# Main-v6_0.net
KiCad netlist of a schematic drawn in EAGLE
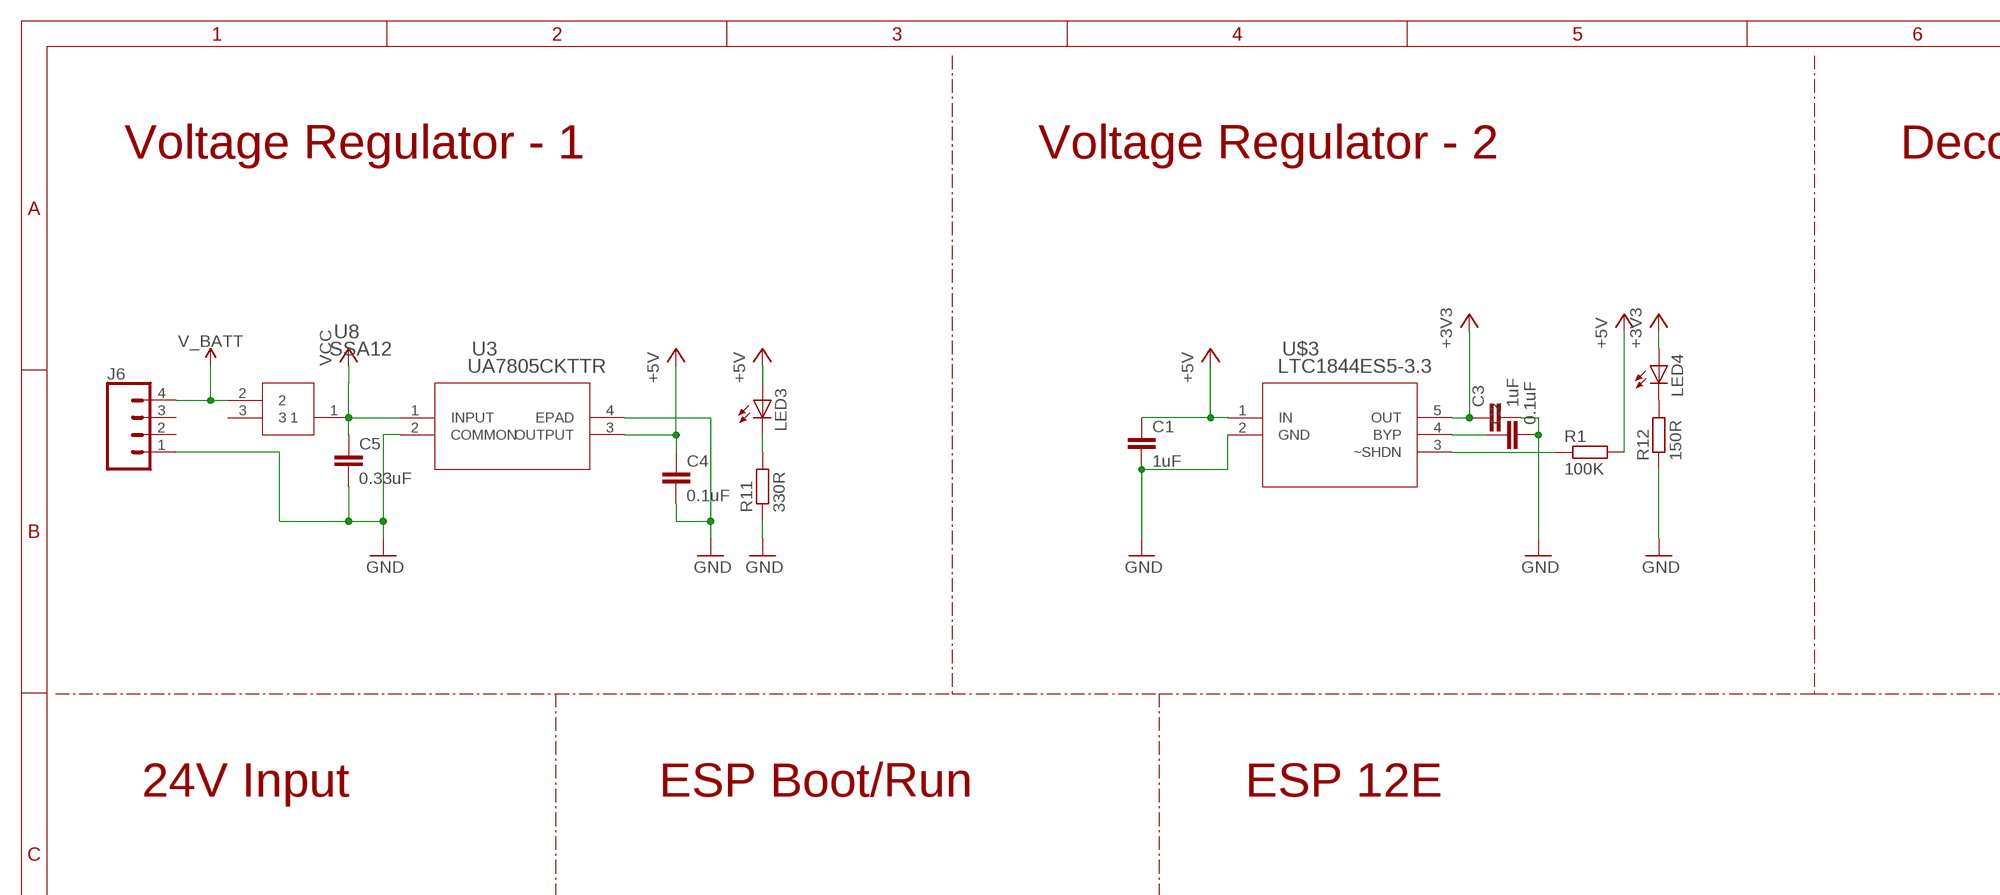
[diagram p0: schematic, sheet 1, part 1 of 3]
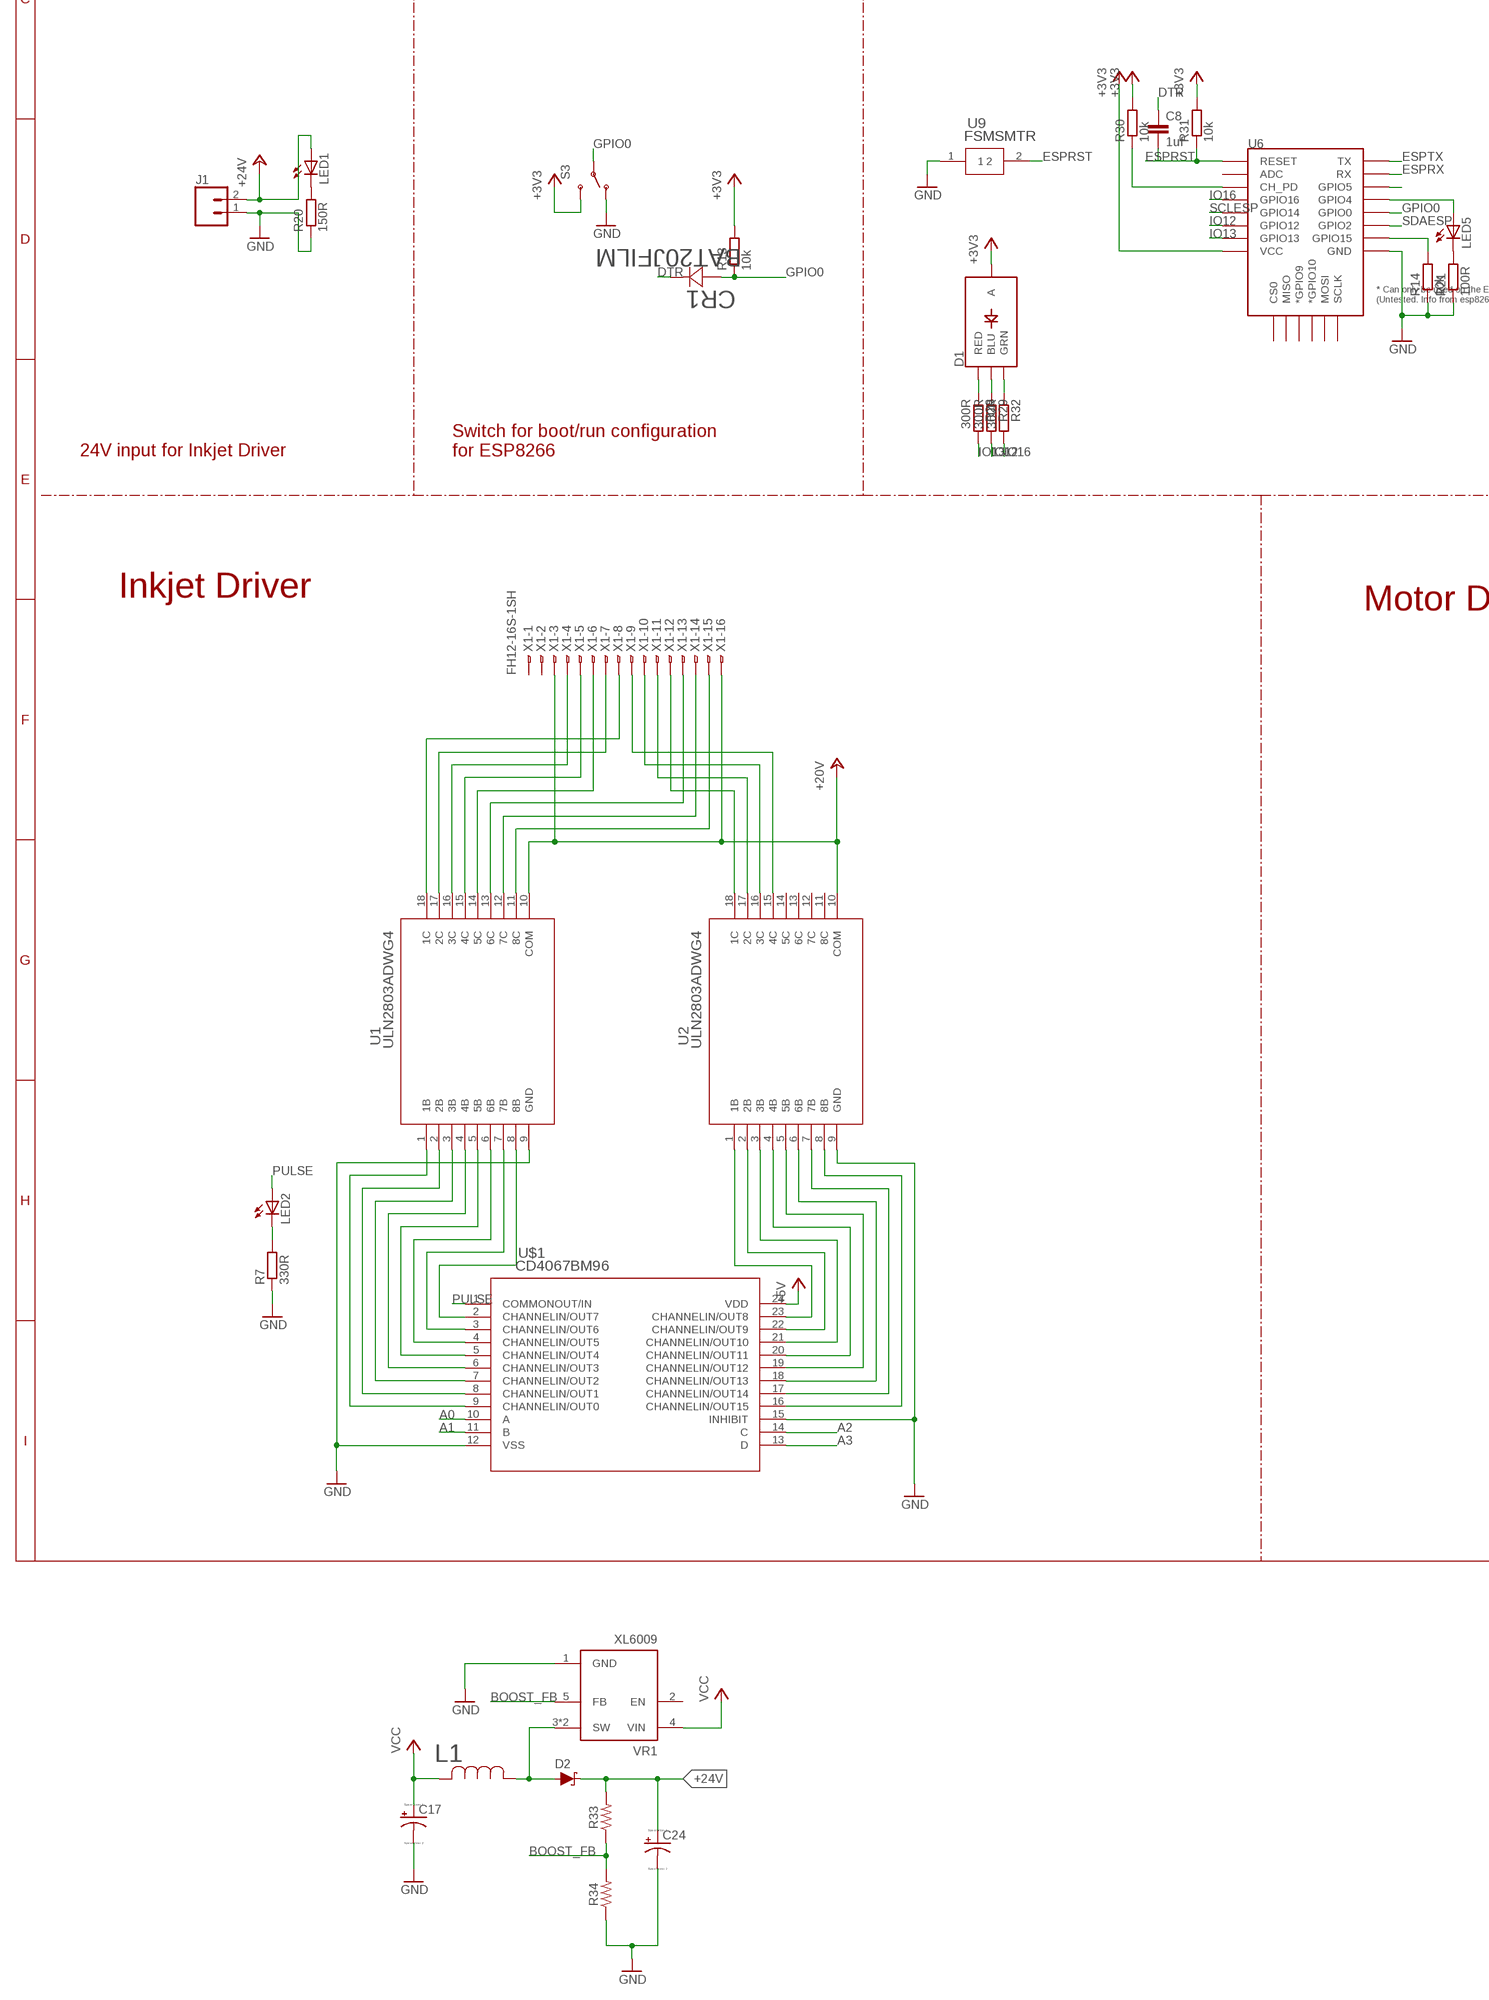
[diagram p1: schematic, sheet 1, part 2 of 3]
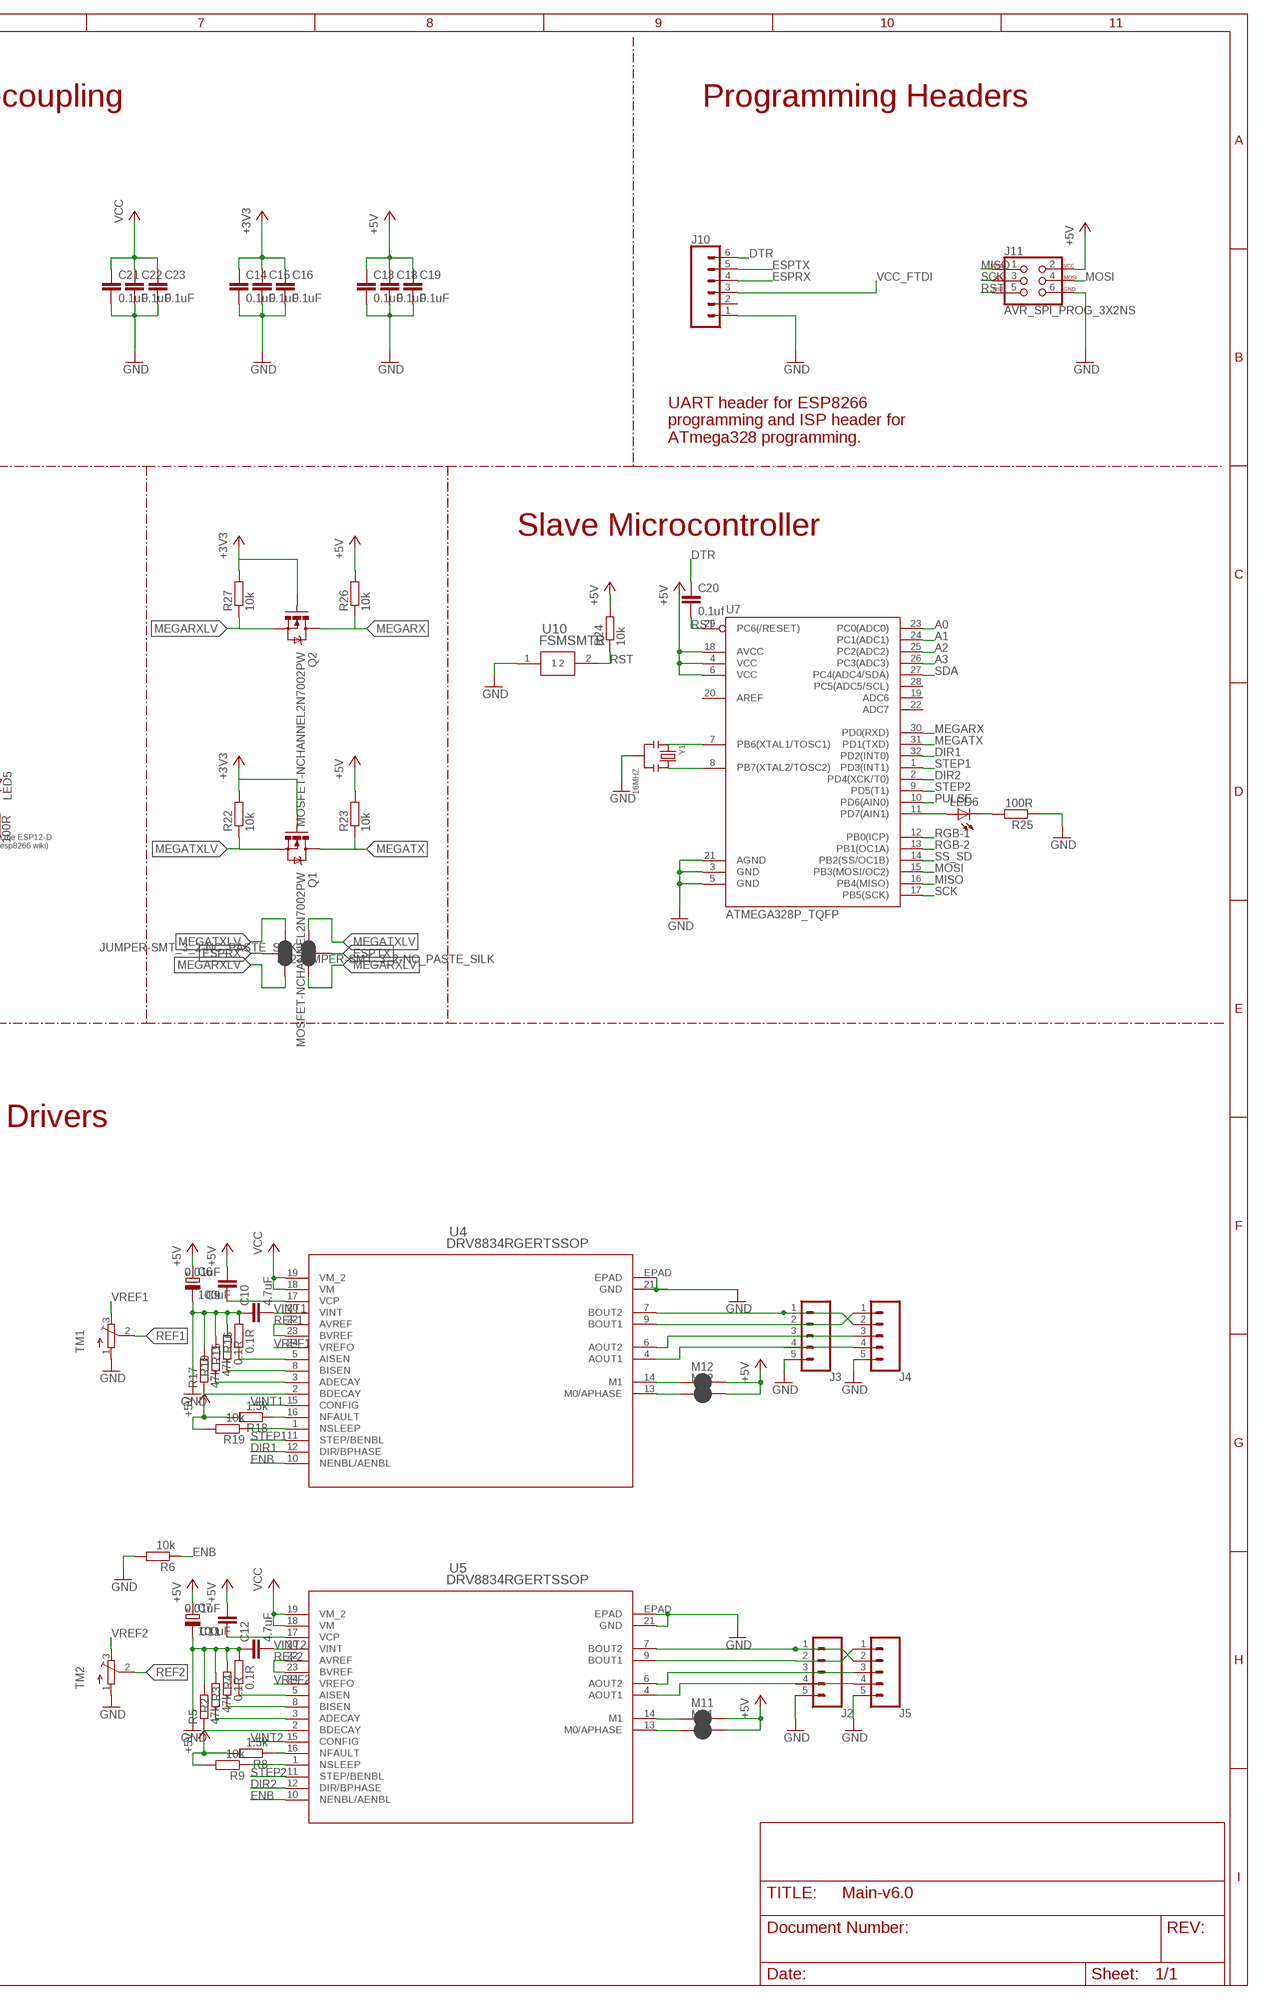
[diagram p2: schematic, sheet 1, part 3 of 3]

(export (version "E")
  (design (tool "Eeschema 10.0.6"))
  (components
    (comp (ref "C1")
      (value "1uF")
      (footprint "eagle-import:C0603")
      (libsource (lib "eagle-import") (part "C-EUC0603"))
    )
    (comp (ref "C2")
      (value "0.1uF")
      (footprint "eagle-import:C0603")
      (libsource (lib "eagle-import") (part "C-EUC0603"))
    )
    (comp (ref "C3")
      (value "1uF")
      (footprint "eagle-import:C0603")
      (libsource (lib "eagle-import") (part "C-EUC0603"))
    )
    (comp (ref "C4")
      (value "0.1uF")
      (footprint "eagle-import:C0603")
      (libsource (lib "eagle-import") (part "C-EUC0603"))
    )
    (comp (ref "C5")
      (value "0.33uF")
      (footprint "eagle-import:C0603")
      (libsource (lib "eagle-import") (part "C-EUC0603"))
    )
    (comp (ref "C6")
      (value "100uF")
      (footprint "eagle-import:E5-5")
      (libsource (lib "eagle-import") (part "CPOL-EUE5-5"))
    )
    (comp (ref "C7")
      (value "100uF")
      (footprint "eagle-import:E5-5")
      (libsource (lib "eagle-import") (part "CPOL-EUE5-5"))
    )
    (comp (ref "C8")
      (value "1uf")
      (footprint "eagle-import:C0603")
      (libsource (lib "eagle-import") (part "resistor_348_C-EUC0603"))
    )
    (comp (ref "C9")
      (value "0.01uF")
      (footprint "eagle-import:C0603K")
      (libsource (lib "eagle-import") (part "resistor_348_C-EUC0603K"))
    )
    (comp (ref "C10")
      (value "4.7uF")
      (footprint "eagle-import:C0603K")
      (libsource (lib "eagle-import") (part "resistor_348_C-EUC0603K"))
    )
    (comp (ref "C11")
      (value "0.01uF")
      (footprint "eagle-import:C0603K")
      (libsource (lib "eagle-import") (part "resistor_348_C-EUC0603K"))
    )
    (comp (ref "C12")
      (value "4.7uF")
      (footprint "eagle-import:C0603K")
      (libsource (lib "eagle-import") (part "resistor_348_C-EUC0603K"))
    )
    (comp (ref "C13")
      (value "0.1uF")
      (footprint "eagle-import:C0603")
      (libsource (lib "eagle-import") (part "C-EUC0603"))
    )
    (comp (ref "C14")
      (value "0.1uF")
      (footprint "eagle-import:C0603")
      (libsource (lib "eagle-import") (part "C-EUC0603"))
    )
    (comp (ref "C15")
      (value "0.1uF")
      (footprint "eagle-import:C0603")
      (libsource (lib "eagle-import") (part "C-EUC0603"))
    )
    (comp (ref "C16")
      (value "0.1uF")
      (footprint "eagle-import:C0603")
      (libsource (lib "eagle-import") (part "C-EUC0603"))
    )
    (comp (ref "C17")
      (value "220uF")
      (footprint "eagle-import:PANASONIC_G")
      (libsource (lib "eagle-import") (part "CPOL-USG"))
    )
    (comp (ref "C18")
      (value "0.1uF")
      (footprint "eagle-import:C0603")
      (libsource (lib "eagle-import") (part "C-EUC0603"))
    )
    (comp (ref "C19")
      (value "0.1uF")
      (footprint "eagle-import:C0603")
      (libsource (lib "eagle-import") (part "C-EUC0603"))
    )
    (comp (ref "C20")
      (value "0.1uf")
      (footprint "eagle-import:C0603")
      (libsource (lib "eagle-import") (part "resistor_348_C-EUC0603"))
    )
    (comp (ref "C21")
      (value "0.1uF")
      (footprint "eagle-import:C0603")
      (libsource (lib "eagle-import") (part "C-EUC0603"))
    )
    (comp (ref "C22")
      (value "0.1uF")
      (footprint "eagle-import:C0603")
      (libsource (lib "eagle-import") (part "C-EUC0603"))
    )
    (comp (ref "C23")
      (value "0.1uF")
      (footprint "eagle-import:C0603")
      (libsource (lib "eagle-import") (part "C-EUC0603"))
    )
    (comp (ref "C24")
      (value "100uF")
      (footprint "eagle-import:PANASONIC_D")
      (libsource (lib "eagle-import") (part "CPOL-USD"))
    )
    (comp (ref "CR1")
      (value "BAT20JFILM")
      (footprint "eagle-import:SOD-323")
      (libsource (lib "eagle-import") (part "BAT20JFILM"))
    )
    (comp (ref "D1")
      (value "LED-RGB-CASMD")
      (footprint "eagle-import:LED-TRICOLOR-SMD")
      (libsource (lib "eagle-import") (part "LED-RGB-CASMD"))
    )
    (comp (ref "D2")
      (value "3A/40V/500mV")
      (footprint "eagle-import:SMA-DIODE")
      (libsource (lib "eagle-import") (part "DIODE-SCHOTTKY-B340A"))
    )
    (comp (ref "J1")
      (value "CONN_02")
      (footprint "eagle-import:1X02")
      (libsource (lib "eagle-import") (part "CONN_02"))
    )
    (comp (ref "J2")
      (value "CONN_05")
      (footprint "eagle-import:1X05")
      (libsource (lib "eagle-import") (part "CONN_05"))
    )
    (comp (ref "J3")
      (value "CONN_05")
      (footprint "eagle-import:1X05")
      (libsource (lib "eagle-import") (part "CONN_05"))
    )
    (comp (ref "J4")
      (value "CONN_05")
      (footprint "eagle-import:1X05")
      (libsource (lib "eagle-import") (part "CONN_05"))
    )
    (comp (ref "J5")
      (value "CONN_05")
      (footprint "eagle-import:1X05")
      (libsource (lib "eagle-import") (part "CONN_05"))
    )
    (comp (ref "J6")
      (value "CONN_04")
      (footprint "eagle-import:1X04")
      (libsource (lib "eagle-import") (part "CONN_04"))
    )
    (comp (ref "J10")
      (value "CONN_06NO_SILK_NO_POP")
      (footprint "eagle-import:1X06_NO_SILK")
      (libsource (lib "eagle-import") (part "CONN_06NO_SILK_NO_POP"))
    )
    (comp (ref "J11")
      (value "AVR_SPI_PROG_3X2NS")
      (footprint "eagle-import:2X3-NS")
      (libsource (lib "eagle-import") (part "AVR_SPI_PROG_3X2NS"))
    )
    (comp (ref "JP1")
      (value "JUMPER-SMT_3_2-NC_PASTE_SILK")
      (footprint "eagle-import:SMT-JUMPER_3_2-NC_PASTE_SILK")
      (libsource (lib "eagle-import") (part "JUMPER-SMT_3_2-NC_PASTE_SILK"))
    )
    (comp (ref "JP2")
      (value "JUMPER-SMT_3_2-NC_PASTE_SILK")
      (footprint "eagle-import:SMT-JUMPER_3_2-NC_PASTE_SILK")
      (libsource (lib "eagle-import") (part "JUMPER-SMT_3_2-NC_PASTE_SILK"))
    )
    (comp (ref "L1")
      (value "SRR1210-680M")
      (footprint "eagle-import:IND_BOURNS_SRR1210")
      (libsource (lib "eagle-import") (part "SRR1210-680M"))
    )
    (comp (ref "LED1")
      (value "LEDSML0603")
      (footprint "eagle-import:SML0603")
      (libsource (lib "eagle-import") (part "LEDSML0603"))
    )
    (comp (ref "LED2")
      (value "LEDSML0603")
      (footprint "eagle-import:SML0603")
      (libsource (lib "eagle-import") (part "LEDSML0603"))
    )
    (comp (ref "LED3")
      (value "LEDSML0603")
      (footprint "eagle-import:SML0603")
      (libsource (lib "eagle-import") (part "LEDSML0603"))
    )
    (comp (ref "LED4")
      (value "LEDSML0603")
      (footprint "eagle-import:SML0603")
      (libsource (lib "eagle-import") (part "LEDSML0603"))
    )
    (comp (ref "LED5")
      (value "LEDSML0603")
      (footprint "eagle-import:SML0603")
      (libsource (lib "eagle-import") (part "LEDSML0603"))
    )
    (comp (ref "LED6")
      (value "LEDSML0603")
      (footprint "eagle-import:SML0603")
      (libsource (lib "eagle-import") (part "LEDSML0603"))
    )
    (comp (ref "M01")
      (value "JUMPER-SMT_2_NC_PASTE_SILK")
      (footprint "eagle-import:SMT-JUMPER_2_NC_PASTE_SILK")
      (libsource (lib "eagle-import") (part "JUMPER-SMT_2_NC_PASTE_SILK"))
    )
    (comp (ref "M02")
      (value "JUMPER-SMT_2_NC_PASTE_SILK")
      (footprint "eagle-import:SMT-JUMPER_2_NC_PASTE_SILK")
      (libsource (lib "eagle-import") (part "JUMPER-SMT_2_NC_PASTE_SILK"))
    )
    (comp (ref "M11")
      (value "JUMPER-SMT_2_NC_PASTE_SILK")
      (footprint "eagle-import:SMT-JUMPER_2_NC_PASTE_SILK")
      (libsource (lib "eagle-import") (part "JUMPER-SMT_2_NC_PASTE_SILK"))
    )
    (comp (ref "M12")
      (value "JUMPER-SMT_2_NC_PASTE_SILK")
      (footprint "eagle-import:SMT-JUMPER_2_NC_PASTE_SILK")
      (libsource (lib "eagle-import") (part "JUMPER-SMT_2_NC_PASTE_SILK"))
    )
    (comp (ref "Q1")
      (value "MOSFET-NCHANNEL2N7002PW")
      (footprint "eagle-import:SOT323")
      (libsource (lib "eagle-import") (part "MOSFET-NCHANNEL2N7002PW"))
    )
    (comp (ref "Q2")
      (value "MOSFET-NCHANNEL2N7002PW")
      (footprint "eagle-import:SOT323")
      (libsource (lib "eagle-import") (part "MOSFET-NCHANNEL2N7002PW"))
    )
    (comp (ref "R1")
      (value "100K")
      (footprint "eagle-import:R0603")
      (libsource (lib "eagle-import") (part "R-EU_R0603"))
    )
    (comp (ref "R2")
      (value "47k")
      (footprint "eagle-import:R0402")
      (libsource (lib "eagle-import") (part "resistor_348_R-EU_R0402"))
    )
    (comp (ref "R3")
      (value "0.1R")
      (footprint "eagle-import:R0402")
      (libsource (lib "eagle-import") (part "resistor_348_R-EU_R0402"))
    )
    (comp (ref "R4")
      (value "0.1R")
      (footprint "eagle-import:R0402")
      (libsource (lib "eagle-import") (part "resistor_348_R-EU_R0402"))
    )
    (comp (ref "R5")
      (value "47k")
      (footprint "eagle-import:R0402")
      (libsource (lib "eagle-import") (part "resistor_348_R-EU_R0402"))
    )
    (comp (ref "R6")
      (value "10k")
      (footprint "eagle-import:R0402")
      (libsource (lib "eagle-import") (part "resistor_348_R-EU_R0402"))
    )
    (comp (ref "R7")
      (value "330R")
      (footprint "eagle-import:R0603")
      (libsource (lib "eagle-import") (part "R-EU_R0603"))
    )
    (comp (ref "R8")
      (value "1.5k")
      (footprint "eagle-import:R0402")
      (libsource (lib "eagle-import") (part "resistor_348_R-EU_R0402"))
    )
    (comp (ref "R9")
      (value "10k")
      (footprint "eagle-import:R0402")
      (libsource (lib "eagle-import") (part "resistor_348_R-EU_R0402"))
    )
    (comp (ref "R10")
      (value "47k")
      (footprint "eagle-import:R0402")
      (libsource (lib "eagle-import") (part "resistor_348_R-EU_R0402"))
    )
    (comp (ref "R11")
      (value "330R")
      (footprint "eagle-import:R0603")
      (libsource (lib "eagle-import") (part "R-EU_R0603"))
    )
    (comp (ref "R12")
      (value "150R")
      (footprint "eagle-import:R0603")
      (libsource (lib "eagle-import") (part "R-EU_R0603"))
    )
    (comp (ref "R13")
      (value "10k")
      (footprint "eagle-import:R0603")
      (libsource (lib "eagle-import") (part "R-EU_R0603"))
    )
    (comp (ref "R14")
      (value "10k")
      (footprint "eagle-import:R0603")
      (libsource (lib "eagle-import") (part "R-EU_R0603"))
    )
    (comp (ref "R15")
      (value "0.1R")
      (footprint "eagle-import:R0402")
      (libsource (lib "eagle-import") (part "resistor_348_R-EU_R0402"))
    )
    (comp (ref "R16")
      (value "0.1R")
      (footprint "eagle-import:R0402")
      (libsource (lib "eagle-import") (part "resistor_348_R-EU_R0402"))
    )
    (comp (ref "R17")
      (value "47k")
      (footprint "eagle-import:R0402")
      (libsource (lib "eagle-import") (part "resistor_348_R-EU_R0402"))
    )
    (comp (ref "R18")
      (value "1.5k")
      (footprint "eagle-import:R0402")
      (libsource (lib "eagle-import") (part "resistor_348_R-EU_R0402"))
    )
    (comp (ref "R19")
      (value "10k")
      (footprint "eagle-import:R0402")
      (libsource (lib "eagle-import") (part "resistor_348_R-EU_R0402"))
    )
    (comp (ref "R20")
      (value "150R")
      (footprint "eagle-import:R0603")
      (libsource (lib "eagle-import") (part "R-EU_R0603"))
    )
    (comp (ref "R21")
      (value "100R")
      (footprint "eagle-import:R0603")
      (libsource (lib "eagle-import") (part "R-EU_R0603"))
    )
    (comp (ref "R22")
      (value "10k")
      (footprint "eagle-import:R0603")
      (libsource (lib "eagle-import") (part "R-EU_R0603"))
    )
    (comp (ref "R23")
      (value "10k")
      (footprint "eagle-import:R0603")
      (libsource (lib "eagle-import") (part "R-EU_R0603"))
    )
    (comp (ref "R24")
      (value "10k")
      (footprint "eagle-import:R0603")
      (libsource (lib "eagle-import") (part "R-EU_R0603"))
    )
    (comp (ref "R25")
      (value "100R")
      (footprint "eagle-import:R0603")
      (libsource (lib "eagle-import") (part "R-EU_R0603"))
    )
    (comp (ref "R26")
      (value "10k")
      (footprint "eagle-import:R0603")
      (libsource (lib "eagle-import") (part "R-EU_R0603"))
    )
    (comp (ref "R27")
      (value "10k")
      (footprint "eagle-import:R0603")
      (libsource (lib "eagle-import") (part "R-EU_R0603"))
    )
    (comp (ref "R28")
      (value "300R")
      (footprint "eagle-import:R0603")
      (libsource (lib "eagle-import") (part "R-EU_R0603"))
    )
    (comp (ref "R29")
      (value "300R")
      (footprint "eagle-import:R0603")
      (libsource (lib "eagle-import") (part "R-EU_R0603"))
    )
    (comp (ref "R30")
      (value "10k")
      (footprint "eagle-import:R0603")
      (libsource (lib "eagle-import") (part "R-EU_R0603"))
    )
    (comp (ref "R31")
      (value "10k")
      (footprint "eagle-import:R0603")
      (libsource (lib "eagle-import") (part "R-EU_R0603"))
    )
    (comp (ref "R32")
      (value "300R")
      (footprint "eagle-import:R0603")
      (libsource (lib "eagle-import") (part "R-EU_R0603"))
    )
    (comp (ref "R33")
      (value "RESISTOR0603")
      (footprint "eagle-import:0603")
      (libsource (lib "eagle-import") (part "RESISTOR0603"))
    )
    (comp (ref "R34")
      (value "RESISTOR0603")
      (footprint "eagle-import:0603")
      (libsource (lib "eagle-import") (part "RESISTOR0603"))
    )
    (comp (ref "S3")
      (value "SWITCH-SPDT-SMD-A")
      (footprint "eagle-import:SWITCH-SPST-SMD-A")
      (libsource (lib "eagle-import") (part "SWITCH-SPDT-SMD-A"))
    )
    (comp (ref "TM1")
      (value "TRIMPOTTC33X")
      (footprint "eagle-import:TC33X")
      (libsource (lib "eagle-import") (part "TRIMPOTTC33X"))
    )
    (comp (ref "TM2")
      (value "TRIMPOTTC33X")
      (footprint "eagle-import:TC33X")
      (libsource (lib "eagle-import") (part "TRIMPOTTC33X"))
    )
    (comp (ref "U$1")
      (value "CD4067BM96")
      (footprint "eagle-import:DW24")
      (fields (field (name "MANUFACTURER_PART_NUMBER") "CD4067B_DW_24"))
      (libsource (lib "eagle-import") (part "CD4067BM96"))
    )
    (comp (ref "U$3")
      (value "LTC1844ES5-3.3")
      (footprint "eagle-import:TSOT-23_S5")
      (libsource (lib "eagle-import") (part "LTC1844ES5-3.3"))
    )
    (comp (ref "U1")
      (value "ULN2803ADWG4")
      (footprint "eagle-import:DW18")
      (libsource (lib "eagle-import") (part "ULN2803ADWG4"))
    )
    (comp (ref "U2")
      (value "ULN2803ADWG4")
      (footprint "eagle-import:DW18")
      (libsource (lib "eagle-import") (part "ULN2803ADWG4"))
    )
    (comp (ref "U3")
      (value "UA7805CKTTR")
      (footprint "eagle-import:KTT3_6P22X6P6")
      (libsource (lib "eagle-import") (part "UA7805CKTTR"))
    )
    (comp (ref "U4")
      (value "DRV8834RGERTSSOP")
      (footprint "eagle-import:PWP_24")
      (libsource (lib "eagle-import") (part "DRV8834RGERTSSOP"))
    )
    (comp (ref "U5")
      (value "DRV8834RGERTSSOP")
      (footprint "eagle-import:PWP_24")
      (libsource (lib "eagle-import") (part "DRV8834RGERTSSOP"))
    )
    (comp (ref "U6")
      (value "ESP12ESMD")
      (footprint "eagle-import:ESP12E-SMD")
      (libsource (lib "eagle-import") (part "ESP12ESMD"))
    )
    (comp (ref "U7")
      (value "ATMEGA328P_TQFP")
      (footprint "eagle-import:TQFP32-08")
      (libsource (lib "eagle-import") (part "ATMEGA328P_TQFP"))
    )
    (comp (ref "U8")
      (value "SSA12")
      (footprint "eagle-import:SWSIP3-P98")
      (libsource (lib "eagle-import") (part "SSA12"))
    )
    (comp (ref "U9")
      (value "FSMSMTR")
      (footprint "eagle-import:SWITCH_FSMSMTR")
      (libsource (lib "eagle-import") (part "FSMSMTR"))
    )
    (comp (ref "U10")
      (value "FSMSMTR")
      (footprint "eagle-import:SWITCH_FSMSMTR")
      (libsource (lib "eagle-import") (part "FSMSMTR"))
    )
    (comp (ref "VR1")
      (value "XL6009")
      (footprint "eagle-import:DPAK170P1435X465-6N")
      (fields (field (name "MF") "XLSEMI"))
      (libsource (lib "eagle-import") (part "XL6009"))
    )
    (comp (ref "X1")
      (value "FH12-16S-1SH")
      (footprint "eagle-import:FH12-16S-1SH")
      (libsource (lib "eagle-import") (part "FH12-16S-1SH"))
    )
    (comp (ref "Y1")
      (value "16MHZ")
      (footprint "eagle-import:X3-SMD-3.6X1.3X0.8MM")
      (fields (field (name "MPN") "CSTCE16M0V53-R0"))
      (libsource (lib "eagle-import") (part "SMD-RESONATOR-16MHZ-15PF-0.5%-40R(3P-3.2X1.3MM)"))
    )
  )
  (nets
    (net (code "1") (name "+3V3") (class "Default")
      (node (ref "C14") (pin "1") (pinfunction "1_1") (pintype "passive"))
      (node (ref "C15") (pin "1") (pinfunction "1_1") (pintype "passive"))
      (node (ref "C16") (pin "1") (pinfunction "1_1") (pintype "passive"))
      (node (ref "C3") (pin "1") (pinfunction "1_1") (pintype "passive"))
      (node (ref "D1") (pin "A") (pinfunction "A_A") (pintype "bidirectional"))
      (node (ref "LED4") (pin "A") (pinfunction "A_A") (pintype "passive"))
      (node (ref "Q1") (pin "1") (pinfunction "G_1") (pintype "passive"))
      (node (ref "Q2") (pin "1") (pinfunction "G_1") (pintype "passive"))
      (node (ref "R13") (pin "2") (pinfunction "2_2") (pintype "passive"))
      (node (ref "R22") (pin "2") (pinfunction "2_2") (pintype "passive"))
      (node (ref "R27") (pin "2") (pinfunction "2_2") (pintype "passive"))
      (node (ref "R30") (pin "2") (pinfunction "2_2") (pintype "passive"))
      (node (ref "R31") (pin "2") (pinfunction "2_2") (pintype "passive"))
      (node (ref "S3") (pin "3") (pinfunction "S_3") (pintype "passive"))
      (node (ref "U$3") (pin "5") (pinfunction "OUT_5") (pintype "passive"))
      (node (ref "U6") (pin "VCC") (pinfunction "VCC_VCC") (pintype "bidirectional"))
    )
    (net (code "2") (name "+5V") (class "Default")
      (node (ref "C1") (pin "1") (pinfunction "1_1") (pintype "passive"))
      (node (ref "C11") (pin "2") (pinfunction "2_2") (pintype "passive"))
      (node (ref "C13") (pin "1") (pinfunction "1_1") (pintype "passive"))
      (node (ref "C18") (pin "1") (pinfunction "1_1") (pintype "passive"))
      (node (ref "C19") (pin "1") (pinfunction "1_1") (pintype "passive"))
      (node (ref "C4") (pin "1") (pinfunction "1_1") (pintype "passive"))
      (node (ref "C6") (pin "+") (pinfunction "+_+") (pintype "passive"))
      (node (ref "C7") (pin "+") (pinfunction "+_+") (pintype "passive"))
      (node (ref "C9") (pin "2") (pinfunction "2_2") (pintype "passive"))
      (node (ref "J11") (pin "2") (pinfunction "2_2") (pintype "passive"))
      (node (ref "LED3") (pin "A") (pinfunction "A_A") (pintype "passive"))
      (node (ref "M01") (pin "2") (pinfunction "2_2") (pintype "passive"))
      (node (ref "M02") (pin "2") (pinfunction "2_2") (pintype "passive"))
      (node (ref "M11") (pin "2") (pinfunction "2_2") (pintype "passive"))
      (node (ref "M12") (pin "2") (pinfunction "2_2") (pintype "passive"))
      (node (ref "R1") (pin "2") (pinfunction "2_2") (pintype "passive"))
      (node (ref "R18") (pin "2") (pinfunction "2_2") (pintype "passive"))
      (node (ref "R19") (pin "2") (pinfunction "2_2") (pintype "passive"))
      (node (ref "R23") (pin "2") (pinfunction "2_2") (pintype "passive"))
      (node (ref "R24") (pin "2") (pinfunction "2_2") (pintype "passive"))
      (node (ref "R26") (pin "2") (pinfunction "2_2") (pintype "passive"))
      (node (ref "R8") (pin "2") (pinfunction "2_2") (pintype "passive"))
      (node (ref "R9") (pin "2") (pinfunction "2_2") (pintype "passive"))
      (node (ref "U$1") (pin "24") (pinfunction "VDD_24") (pintype "power_in"))
      (node (ref "U$3") (pin "1") (pinfunction "IN_1") (pintype "passive"))
      (node (ref "U3") (pin "3") (pinfunction "OUTPUT_3") (pintype "output"))
      (node (ref "U7") (pin "18") (pinfunction "AVCC_18") (pintype "bidirectional"))
      (node (ref "U7") (pin "4") (pinfunction "VCC_4") (pintype "bidirectional"))
      (node (ref "U7") (pin "6") (pinfunction "VCC_6") (pintype "bidirectional"))
    )
    (net (code "3") (name "+24V") (class "Default")
      (node (ref "C24") (pin "+") (pinfunction "+_+") (pintype "passive"))
      (node (ref "D2") (pin "C") (pinfunction "C_C") (pintype "passive"))
      (node (ref "J1") (pin "2") (pinfunction "2_2") (pintype "passive"))
      (node (ref "LED1") (pin "A") (pinfunction "A_A") (pintype "passive"))
      (node (ref "R33") (pin "2") (pinfunction "2_2") (pintype "passive"))
      (node (ref "U1") (pin "10") (pinfunction "COM_10") (pintype "passive"))
      (node (ref "U2") (pin "10") (pinfunction "COM_10") (pintype "passive"))
      (node (ref "X1") (pin "16") (pinfunction "1_16") (pintype "passive"))
      (node (ref "X1") (pin "3") (pinfunction "1_3") (pintype "passive"))
    )
    (net (code "4") (name "/A0") (class "Default")
      (node (ref "U$1") (pin "10") (pinfunction "A_10") (pintype "passive"))
      (node (ref "U7") (pin "23") (pinfunction "PC0(ADC0)_23") (pintype "bidirectional"))
    )
    (net (code "5") (name "/A1") (class "Default")
      (node (ref "U$1") (pin "11") (pinfunction "B_11") (pintype "passive"))
      (node (ref "U7") (pin "24") (pinfunction "PC1(ADC1)_24") (pintype "bidirectional"))
    )
    (net (code "6") (name "/A2") (class "Default")
      (node (ref "U$1") (pin "14") (pinfunction "C_14") (pintype "passive"))
      (node (ref "U7") (pin "25") (pinfunction "PC2(ADC2)_25") (pintype "bidirectional"))
    )
    (net (code "7") (name "/A3") (class "Default")
      (node (ref "U$1") (pin "13") (pinfunction "D_13") (pintype "passive"))
      (node (ref "U7") (pin "26") (pinfunction "PC3(ADC3)_26") (pintype "bidirectional"))
    )
    (net (code "8") (name "/BOOST_FB") (class "Default")
      (node (ref "R33") (pin "1") (pinfunction "1_1") (pintype "passive"))
      (node (ref "R34") (pin "2") (pinfunction "2_2") (pintype "passive"))
      (node (ref "VR1") (pin "5") (pinfunction "FB_5") (pintype "input"))
    )
    (net (code "9") (name "/DIR1") (class "Default")
      (node (ref "U4") (pin "12") (pinfunction "DIR/BPHASE_12") (pintype "input"))
      (node (ref "U7") (pin "32") (pinfunction "PD2(INT0)_32") (pintype "bidirectional"))
    )
    (net (code "10") (name "/DIR2") (class "Default")
      (node (ref "U5") (pin "12") (pinfunction "DIR/BPHASE_12") (pintype "input"))
      (node (ref "U7") (pin "2") (pinfunction "PD4(XCK/T0)_2") (pintype "bidirectional"))
    )
    (net (code "11") (name "/DTR") (class "Default")
      (node (ref "C20") (pin "1") (pinfunction "1_1") (pintype "passive"))
      (node (ref "C8") (pin "1") (pinfunction "1_1") (pintype "passive"))
      (node (ref "CR1") (pin "1") (pinfunction "11_1") (pintype "passive"))
      (node (ref "J10") (pin "6") (pinfunction "6_6") (pintype "passive"))
    )
    (net (code "12") (name "/ENB") (class "Default")
      (node (ref "R6") (pin "1") (pinfunction "1_1") (pintype "passive"))
      (node (ref "U4") (pin "10") (pinfunction "NENBL/AENBL_10") (pintype "input"))
      (node (ref "U5") (pin "10") (pinfunction "NENBL/AENBL_10") (pintype "input"))
    )
    (net (code "13") (name "/ESPRST") (class "Default")
      (node (ref "C8") (pin "2") (pinfunction "2_2") (pintype "passive"))
      (node (ref "R31") (pin "1") (pinfunction "1_1") (pintype "passive"))
      (node (ref "U6") (pin "RESET") (pinfunction "RESET_RESET") (pintype "bidirectional"))
      (node (ref "U9") (pin "2") (pinfunction "2_2") (pintype "passive"))
    )
    (net (code "14") (name "/GPIO0") (class "Default")
      (node (ref "CR1") (pin "2") (pinfunction "22_2") (pintype "passive"))
      (node (ref "R13") (pin "1") (pinfunction "1_1") (pintype "passive"))
      (node (ref "S3") (pin "2") (pinfunction "P_2") (pintype "passive"))
      (node (ref "U6") (pin "GPIO0") (pinfunction "GPIO0_GPIO0") (pintype "bidirectional"))
    )
    (net (code "15") (name "/IO12") (class "Default")
      (node (ref "R29") (pin "2") (pinfunction "2_2") (pintype "passive"))
      (node (ref "U6") (pin "GPIO12") (pinfunction "GPIO12_GPIO12") (pintype "bidirectional"))
    )
    (net (code "16") (name "/IO13") (class "Default")
      (node (ref "R28") (pin "2") (pinfunction "2_2") (pintype "passive"))
      (node (ref "U6") (pin "GPIO13") (pinfunction "GPIO13_GPIO13") (pintype "bidirectional"))
    )
    (net (code "17") (name "/IO16") (class "Default")
      (node (ref "R32") (pin "2") (pinfunction "2_2") (pintype "passive"))
      (node (ref "U6") (pin "GPIO16") (pinfunction "GPIO16_GPIO16") (pintype "bidirectional"))
    )
    (net (code "18") (name "/MISO") (class "Default")
      (node (ref "J11") (pin "1") (pinfunction "1_1") (pintype "passive"))
      (node (ref "U7") (pin "16") (pinfunction "PB4(MISO)_16") (pintype "bidirectional"))
    )
    (net (code "19") (name "/MOSI") (class "Default")
      (node (ref "J11") (pin "4") (pinfunction "4_4") (pintype "passive"))
      (node (ref "U7") (pin "15") (pinfunction "PB3(MOSI/OC2)_15") (pintype "bidirectional"))
    )
    (net (code "20") (name "/PULSE") (class "Default")
      (node (ref "LED2") (pin "A") (pinfunction "A_A") (pintype "passive"))
      (node (ref "U$1") (pin "1") (pinfunction "COMMONOUT/IN_1") (pintype "bidirectional"))
      (node (ref "U7") (pin "10") (pinfunction "PD6(AIN0)_10") (pintype "bidirectional"))
    )
    (net (code "21") (name "/RGB-1") (class "Default")
      (node (ref "U7") (pin "12") (pinfunction "PB0(ICP)_12") (pintype "bidirectional"))
    )
    (net (code "22") (name "/RGB-2") (class "Default")
      (node (ref "U7") (pin "13") (pinfunction "PB1(OC1A)_13") (pintype "bidirectional"))
    )
    (net (code "23") (name "/RST") (class "Default")
      (node (ref "C20") (pin "2") (pinfunction "2_2") (pintype "passive"))
      (node (ref "J11") (pin "5") (pinfunction "5_5") (pintype "passive"))
      (node (ref "R24") (pin "1") (pinfunction "1_1") (pintype "passive"))
      (node (ref "U10") (pin "2") (pinfunction "2_2") (pintype "passive"))
      (node (ref "U7") (pin "29") (pinfunction "PC6(/RESET)_29") (pintype "bidirectional"))
    )
    (net (code "24") (name "/SCK") (class "Default")
      (node (ref "J11") (pin "3") (pinfunction "3_3") (pintype "passive"))
      (node (ref "U7") (pin "17") (pinfunction "PB5(SCK)_17") (pintype "bidirectional"))
    )
    (net (code "25") (name "/SCLESP") (class "Default")
      (node (ref "U6") (pin "GPIO14") (pinfunction "GPIO14_GPIO14") (pintype "bidirectional"))
    )
    (net (code "26") (name "/SDA") (class "Default")
      (node (ref "U7") (pin "27") (pinfunction "PC4(ADC4/SDA)_27") (pintype "bidirectional"))
    )
    (net (code "27") (name "/SDAESP") (class "Default")
      (node (ref "U6") (pin "GPIO2") (pinfunction "GPIO2_GPIO2") (pintype "bidirectional"))
    )
    (net (code "28") (name "/SS_SD") (class "Default")
      (node (ref "U7") (pin "14") (pinfunction "PB2(SS/OC1B)_14") (pintype "bidirectional"))
    )
    (net (code "29") (name "/STEP1") (class "Default")
      (node (ref "U4") (pin "11") (pinfunction "STEP/BENBL_11") (pintype "input"))
      (node (ref "U7") (pin "1") (pinfunction "PD3(INT1)_1") (pintype "bidirectional"))
    )
    (net (code "30") (name "/STEP2") (class "Default")
      (node (ref "U5") (pin "11") (pinfunction "STEP/BENBL_11") (pintype "input"))
      (node (ref "U7") (pin "9") (pinfunction "PD5(T1)_9") (pintype "bidirectional"))
    )
    (net (code "31") (name "/VCC_FTDI") (class "Default")
      (node (ref "J10") (pin "3") (pinfunction "3_3") (pintype "passive"))
    )
    (net (code "32") (name "/VINT1") (class "Default")
      (node (ref "C10") (pin "2") (pinfunction "2_2") (pintype "passive"))
      (node (ref "U4") (pin "15") (pinfunction "CONFIG_15") (pintype "input"))
      (node (ref "U4") (pin "20") (pinfunction "VINT_20") (pintype "passive"))
    )
    (net (code "33") (name "/VINT2") (class "Default")
      (node (ref "C12") (pin "2") (pinfunction "2_2") (pintype "passive"))
      (node (ref "U5") (pin "15") (pinfunction "CONFIG_15") (pintype "input"))
      (node (ref "U5") (pin "20") (pinfunction "VINT_20") (pintype "passive"))
    )
    (net (code "34") (name "/VREF1") (class "Default")
      (node (ref "TM1") (pin "3") (pinfunction "E_3") (pintype "passive"))
      (node (ref "U4") (pin "24") (pinfunction "VREFO_24") (pintype "output"))
    )
    (net (code "35") (name "/VREF2") (class "Default")
      (node (ref "TM2") (pin "3") (pinfunction "E_3") (pintype "passive"))
      (node (ref "U5") (pin "24") (pinfunction "VREFO_24") (pintype "output"))
    )
    (net (code "36") (name "ESPRX") (class "Default")
      (node (ref "J10") (pin "4") (pinfunction "4_4") (pintype "passive"))
      (node (ref "JP1") (pin "2") (pinfunction "2_2") (pintype "passive"))
      (node (ref "U6") (pin "RXD0") (pinfunction "RX_RXD0") (pintype "bidirectional"))
    )
    (net (code "37") (name "ESPTX") (class "Default")
      (node (ref "J10") (pin "5") (pinfunction "5_5") (pintype "passive"))
      (node (ref "JP2") (pin "2") (pinfunction "2_2") (pintype "passive"))
      (node (ref "U6") (pin "TXD0") (pinfunction "TX_TXD0") (pintype "bidirectional"))
    )
    (net (code "38") (name "GND") (class "Default")
      (node (ref "C1") (pin "2") (pinfunction "2_2") (pintype "passive"))
      (node (ref "C10") (pin "1") (pinfunction "1_1") (pintype "passive"))
      (node (ref "C12") (pin "1") (pinfunction "1_1") (pintype "passive"))
      (node (ref "C13") (pin "2") (pinfunction "2_2") (pintype "passive"))
      (node (ref "C14") (pin "2") (pinfunction "2_2") (pintype "passive"))
      (node (ref "C15") (pin "2") (pinfunction "2_2") (pintype "passive"))
      (node (ref "C16") (pin "2") (pinfunction "2_2") (pintype "passive"))
      (node (ref "C17") (pin "-") (pinfunction "-_-") (pintype "passive"))
      (node (ref "C18") (pin "2") (pinfunction "2_2") (pintype "passive"))
      (node (ref "C19") (pin "2") (pinfunction "2_2") (pintype "passive"))
      (node (ref "C2") (pin "2") (pinfunction "2_2") (pintype "passive"))
      (node (ref "C21") (pin "2") (pinfunction "2_2") (pintype "passive"))
      (node (ref "C22") (pin "2") (pinfunction "2_2") (pintype "passive"))
      (node (ref "C23") (pin "2") (pinfunction "2_2") (pintype "passive"))
      (node (ref "C24") (pin "-") (pinfunction "-_-") (pintype "passive"))
      (node (ref "C3") (pin "2") (pinfunction "2_2") (pintype "passive"))
      (node (ref "C4") (pin "2") (pinfunction "2_2") (pintype "passive"))
      (node (ref "C5") (pin "2") (pinfunction "2_2") (pintype "passive"))
      (node (ref "C6") (pin "-") (pinfunction "-_-") (pintype "passive"))
      (node (ref "C7") (pin "-") (pinfunction "-_-") (pintype "passive"))
      (node (ref "J1") (pin "1") (pinfunction "1_1") (pintype "passive"))
      (node (ref "J10") (pin "1") (pinfunction "1_1") (pintype "passive"))
      (node (ref "J11") (pin "6") (pinfunction "6_6") (pintype "passive"))
      (node (ref "J2") (pin "5") (pinfunction "5_5") (pintype "passive"))
      (node (ref "J3") (pin "5") (pinfunction "5_5") (pintype "passive"))
      (node (ref "J4") (pin "5") (pinfunction "5_5") (pintype "passive"))
      (node (ref "J5") (pin "5") (pinfunction "5_5") (pintype "passive"))
      (node (ref "J6") (pin "1") (pinfunction "1_1") (pintype "passive"))
      (node (ref "R10") (pin "2") (pinfunction "2_2") (pintype "passive"))
      (node (ref "R11") (pin "1") (pinfunction "1_1") (pintype "passive"))
      (node (ref "R12") (pin "1") (pinfunction "1_1") (pintype "passive"))
      (node (ref "R14") (pin "1") (pinfunction "1_1") (pintype "passive"))
      (node (ref "R15") (pin "2") (pinfunction "2_2") (pintype "passive"))
      (node (ref "R16") (pin "2") (pinfunction "2_2") (pintype "passive"))
      (node (ref "R17") (pin "2") (pinfunction "2_2") (pintype "passive"))
      (node (ref "R2") (pin "2") (pinfunction "2_2") (pintype "passive"))
      (node (ref "R20") (pin "1") (pinfunction "1_1") (pintype "passive"))
      (node (ref "R21") (pin "1") (pinfunction "1_1") (pintype "passive"))
      (node (ref "R25") (pin "1") (pinfunction "1_1") (pintype "passive"))
      (node (ref "R3") (pin "2") (pinfunction "2_2") (pintype "passive"))
      (node (ref "R34") (pin "1") (pinfunction "1_1") (pintype "passive"))
      (node (ref "R4") (pin "2") (pinfunction "2_2") (pintype "passive"))
      (node (ref "R5") (pin "2") (pinfunction "2_2") (pintype "passive"))
      (node (ref "R6") (pin "2") (pinfunction "2_2") (pintype "passive"))
      (node (ref "R7") (pin "1") (pinfunction "1_1") (pintype "passive"))
      (node (ref "S3") (pin "1") (pinfunction "O_1") (pintype "passive"))
      (node (ref "TM1") (pin "1") (pinfunction "A_1") (pintype "passive"))
      (node (ref "TM2") (pin "1") (pinfunction "A_1") (pintype "passive"))
      (node (ref "U$1") (pin "12") (pinfunction "VSS_12") (pintype "power_in"))
      (node (ref "U$1") (pin "15") (pinfunction "INHIBIT_15") (pintype "passive"))
      (node (ref "U$3") (pin "2") (pinfunction "GND_2") (pintype "passive"))
      (node (ref "U1") (pin "9") (pinfunction "GND_9") (pintype "passive"))
      (node (ref "U10") (pin "1") (pinfunction "1_1") (pintype "passive"))
      (node (ref "U2") (pin "9") (pinfunction "GND_9") (pintype "passive"))
      (node (ref "U3") (pin "2") (pinfunction "COMMON_2") (pintype "power_in"))
      (node (ref "U3") (pin "4") (pinfunction "EPAD_4") (pintype "passive"))
      (node (ref "U4") (pin "21") (pinfunction "GND_21") (pintype "power_in"))
      (node (ref "U4") (pin "EPAD") (pinfunction "EPAD_EPAD") (pintype "passive"))
      (node (ref "U5") (pin "21") (pinfunction "GND_21") (pintype "power_in"))
      (node (ref "U5") (pin "EPAD") (pinfunction "EPAD_EPAD") (pintype "passive"))
      (node (ref "U6") (pin "GND") (pinfunction "GND_GND") (pintype "bidirectional"))
      (node (ref "U7") (pin "21") (pinfunction "AGND_21") (pintype "bidirectional"))
      (node (ref "U7") (pin "3") (pinfunction "GND_3") (pintype "bidirectional"))
      (node (ref "U7") (pin "5") (pinfunction "GND_5") (pintype "bidirectional"))
      (node (ref "U9") (pin "1") (pinfunction "1_1") (pintype "passive"))
      (node (ref "VR1") (pin "1") (pinfunction "GND_1") (pintype "power_in"))
      (node (ref "Y1") (pin "2") (pinfunction "2_2") (pintype "passive"))
    )
    (net (code "39") (name "MEGARX") (class "Default")
      (node (ref "Q2") (pin "3") (pinfunction "D_3") (pintype "passive"))
      (node (ref "R26") (pin "1") (pinfunction "1_1") (pintype "passive"))
      (node (ref "U7") (pin "30") (pinfunction "PD0(RXD)_30") (pintype "bidirectional"))
    )
    (net (code "40") (name "MEGARXLV") (class "Default")
      (node (ref "JP1") (pin "3") (pinfunction "3_3") (pintype "passive"))
      (node (ref "JP2") (pin "1") (pinfunction "1_1") (pintype "passive"))
      (node (ref "Q2") (pin "2") (pinfunction "S_2") (pintype "passive"))
      (node (ref "R27") (pin "1") (pinfunction "1_1") (pintype "passive"))
    )
    (net (code "41") (name "MEGATX") (class "Default")
      (node (ref "Q1") (pin "3") (pinfunction "D_3") (pintype "passive"))
      (node (ref "R23") (pin "1") (pinfunction "1_1") (pintype "passive"))
      (node (ref "U7") (pin "31") (pinfunction "PD1(TXD)_31") (pintype "bidirectional"))
    )
    (net (code "42") (name "MEGATXLV") (class "Default")
      (node (ref "JP1") (pin "1") (pinfunction "1_1") (pintype "passive"))
      (node (ref "JP2") (pin "3") (pinfunction "3_3") (pintype "passive"))
      (node (ref "Q1") (pin "2") (pinfunction "S_2") (pintype "passive"))
      (node (ref "R22") (pin "1") (pinfunction "1_1") (pintype "passive"))
    )
    (net (code "43") (name "Net-(D1-BLU)") (class "Default")
      (node (ref "D1") (pin "B") (pinfunction "BLU_B") (pintype "bidirectional"))
      (node (ref "R29") (pin "1") (pinfunction "1_1") (pintype "passive"))
    )
    (net (code "44") (name "Net-(D1-GRN)") (class "Default")
      (node (ref "D1") (pin "G") (pinfunction "GRN_G") (pintype "bidirectional"))
      (node (ref "R32") (pin "1") (pinfunction "1_1") (pintype "passive"))
    )
    (net (code "45") (name "Net-(D1-RED)") (class "Default")
      (node (ref "D1") (pin "R") (pinfunction "RED_R") (pintype "bidirectional"))
      (node (ref "R28") (pin "1") (pinfunction "1_1") (pintype "passive"))
    )
    (net (code "46") (name "Net-(D2-PadA)") (class "Default")
      (node (ref "D2") (pin "A") (pinfunction "A_A") (pintype "passive"))
      (node (ref "L1") (pin "1") (pinfunction "1_1") (pintype "passive"))
      (node (ref "VR1") (pin "3") (pinfunction "SW_3") (pintype "output"))
      (node (ref "VR1") (pin "6") (pinfunction "SW_6") (pintype "output"))
    )
    (net (code "47") (name "Net-(LED1-PadC)") (class "Default")
      (node (ref "LED1") (pin "C") (pinfunction "C_C") (pintype "passive"))
      (node (ref "R20") (pin "2") (pinfunction "2_2") (pintype "passive"))
    )
    (net (code "48") (name "Net-(LED2-PadC)") (class "Default")
      (node (ref "LED2") (pin "C") (pinfunction "C_C") (pintype "passive"))
      (node (ref "R7") (pin "2") (pinfunction "2_2") (pintype "passive"))
    )
    (net (code "49") (name "Net-(LED3-PadC)") (class "Default")
      (node (ref "LED3") (pin "C") (pinfunction "C_C") (pintype "passive"))
      (node (ref "R11") (pin "2") (pinfunction "2_2") (pintype "passive"))
    )
    (net (code "50") (name "Net-(LED4-PadC)") (class "Default")
      (node (ref "LED4") (pin "C") (pinfunction "C_C") (pintype "passive"))
      (node (ref "R12") (pin "2") (pinfunction "2_2") (pintype "passive"))
    )
    (net (code "51") (name "Net-(LED5-PadA)") (class "Default")
      (node (ref "LED5") (pin "A") (pinfunction "A_A") (pintype "passive"))
      (node (ref "U6") (pin "GPIO4") (pinfunction "GPIO4_GPIO4") (pintype "bidirectional"))
    )
    (net (code "52") (name "Net-(LED5-PadC)") (class "Default")
      (node (ref "LED5") (pin "C") (pinfunction "C_C") (pintype "passive"))
      (node (ref "R21") (pin "2") (pinfunction "2_2") (pintype "passive"))
    )
    (net (code "53") (name "Net-(LED6-PadC)") (class "Default")
      (node (ref "LED6") (pin "C") (pinfunction "C_C") (pintype "passive"))
      (node (ref "R25") (pin "2") (pinfunction "2_2") (pintype "passive"))
    )
    (net (code "54") (name "Net-(R14-Pad2)") (class "Default")
      (node (ref "R14") (pin "2") (pinfunction "2_2") (pintype "passive"))
      (node (ref "U6") (pin "GPIO15") (pinfunction "GPIO15_GPIO15") (pintype "bidirectional"))
    )
    (net (code "55") (name "Net-(R30-Pad1)") (class "Default")
      (node (ref "R30") (pin "1") (pinfunction "1_1") (pintype "passive"))
      (node (ref "U6") (pin "CH_PD") (pinfunction "CH_PD_CH_PD") (pintype "bidirectional"))
    )
    (net (code "56") (name "Net-(U$1-CHANNELIN{slash}OUT0)") (class "Default")
      (node (ref "U$1") (pin "9") (pinfunction "CHANNELIN/OUT0_9") (pintype "bidirectional"))
      (node (ref "U1") (pin "1") (pinfunction "1B_1") (pintype "passive"))
    )
    (net (code "57") (name "Net-(U$1-CHANNELIN{slash}OUT1)") (class "Default")
      (node (ref "U$1") (pin "8") (pinfunction "CHANNELIN/OUT1_8") (pintype "bidirectional"))
      (node (ref "U1") (pin "2") (pinfunction "2B_2") (pintype "passive"))
    )
    (net (code "58") (name "Net-(U$1-CHANNELIN{slash}OUT2)") (class "Default")
      (node (ref "U$1") (pin "7") (pinfunction "CHANNELIN/OUT2_7") (pintype "bidirectional"))
      (node (ref "U1") (pin "3") (pinfunction "3B_3") (pintype "passive"))
    )
    (net (code "59") (name "Net-(U$1-CHANNELIN{slash}OUT3)") (class "Default")
      (node (ref "U$1") (pin "6") (pinfunction "CHANNELIN/OUT3_6") (pintype "bidirectional"))
      (node (ref "U1") (pin "4") (pinfunction "4B_4") (pintype "passive"))
    )
    (net (code "60") (name "Net-(U$1-CHANNELIN{slash}OUT4)") (class "Default")
      (node (ref "U$1") (pin "5") (pinfunction "CHANNELIN/OUT4_5") (pintype "bidirectional"))
      (node (ref "U1") (pin "5") (pinfunction "5B_5") (pintype "passive"))
    )
    (net (code "61") (name "Net-(U$1-CHANNELIN{slash}OUT5)") (class "Default")
      (node (ref "U$1") (pin "4") (pinfunction "CHANNELIN/OUT5_4") (pintype "bidirectional"))
      (node (ref "U1") (pin "6") (pinfunction "6B_6") (pintype "passive"))
    )
    (net (code "62") (name "Net-(U$1-CHANNELIN{slash}OUT6)") (class "Default")
      (node (ref "U$1") (pin "3") (pinfunction "CHANNELIN/OUT6_3") (pintype "bidirectional"))
      (node (ref "U1") (pin "7") (pinfunction "7B_7") (pintype "passive"))
    )
    (net (code "63") (name "Net-(U$1-CHANNELIN{slash}OUT7)") (class "Default")
      (node (ref "U$1") (pin "2") (pinfunction "CHANNELIN/OUT7_2") (pintype "bidirectional"))
      (node (ref "U1") (pin "8") (pinfunction "8B_8") (pintype "passive"))
    )
    (net (code "64") (name "Net-(U$1-CHANNELIN{slash}OUT8)") (class "Default")
      (node (ref "U$1") (pin "23") (pinfunction "CHANNELIN/OUT8_23") (pintype "bidirectional"))
      (node (ref "U2") (pin "1") (pinfunction "1B_1") (pintype "passive"))
    )
    (net (code "65") (name "Net-(U$1-CHANNELIN{slash}OUT9)") (class "Default")
      (node (ref "U$1") (pin "22") (pinfunction "CHANNELIN/OUT9_22") (pintype "bidirectional"))
      (node (ref "U2") (pin "2") (pinfunction "2B_2") (pintype "passive"))
    )
    (net (code "66") (name "Net-(U$1-CHANNELIN{slash}OUT10)") (class "Default")
      (node (ref "U$1") (pin "21") (pinfunction "CHANNELIN/OUT10_21") (pintype "bidirectional"))
      (node (ref "U2") (pin "3") (pinfunction "3B_3") (pintype "passive"))
    )
    (net (code "67") (name "Net-(U$1-CHANNELIN{slash}OUT11)") (class "Default")
      (node (ref "U$1") (pin "20") (pinfunction "CHANNELIN/OUT11_20") (pintype "bidirectional"))
      (node (ref "U2") (pin "4") (pinfunction "4B_4") (pintype "passive"))
    )
    (net (code "68") (name "Net-(U$1-CHANNELIN{slash}OUT12)") (class "Default")
      (node (ref "U$1") (pin "19") (pinfunction "CHANNELIN/OUT12_19") (pintype "bidirectional"))
      (node (ref "U2") (pin "5") (pinfunction "5B_5") (pintype "passive"))
    )
    (net (code "69") (name "Net-(U$1-CHANNELIN{slash}OUT13)") (class "Default")
      (node (ref "U$1") (pin "18") (pinfunction "CHANNELIN/OUT13_18") (pintype "bidirectional"))
      (node (ref "U2") (pin "6") (pinfunction "6B_6") (pintype "passive"))
    )
    (net (code "70") (name "Net-(U$1-CHANNELIN{slash}OUT14)") (class "Default")
      (node (ref "U$1") (pin "17") (pinfunction "CHANNELIN/OUT14_17") (pintype "bidirectional"))
      (node (ref "U2") (pin "7") (pinfunction "7B_7") (pintype "passive"))
    )
    (net (code "71") (name "Net-(U$1-CHANNELIN{slash}OUT15)") (class "Default")
      (node (ref "U$1") (pin "16") (pinfunction "CHANNELIN/OUT15_16") (pintype "bidirectional"))
      (node (ref "U2") (pin "8") (pinfunction "8B_8") (pintype "passive"))
    )
    (net (code "72") (name "Net-(U$3-BYP)") (class "Default")
      (node (ref "C2") (pin "1") (pinfunction "1_1") (pintype "passive"))
      (node (ref "U$3") (pin "4") (pinfunction "BYP_4") (pintype "passive"))
    )
    (net (code "73") (name "Net-(U$3-~{SHDN})") (class "Default")
      (node (ref "R1") (pin "1") (pinfunction "1_1") (pintype "passive"))
      (node (ref "U$3") (pin "3") (pinfunction "~{SHDN}_3") (pintype "passive"))
    )
    (net (code "74") (name "Net-(U1-1C)") (class "Default")
      (node (ref "U1") (pin "18") (pinfunction "1C_18") (pintype "passive"))
      (node (ref "X1") (pin "8") (pinfunction "1_8") (pintype "passive"))
    )
    (net (code "75") (name "Net-(U1-2C)") (class "Default")
      (node (ref "U1") (pin "17") (pinfunction "2C_17") (pintype "passive"))
      (node (ref "X1") (pin "7") (pinfunction "1_7") (pintype "passive"))
    )
    (net (code "76") (name "Net-(U1-3C)") (class "Default")
      (node (ref "U1") (pin "16") (pinfunction "3C_16") (pintype "passive"))
      (node (ref "X1") (pin "4") (pinfunction "1_4") (pintype "passive"))
    )
    (net (code "77") (name "Net-(U1-4C)") (class "Default")
      (node (ref "U1") (pin "15") (pinfunction "4C_15") (pintype "passive"))
      (node (ref "X1") (pin "5") (pinfunction "1_5") (pintype "passive"))
    )
    (net (code "78") (name "Net-(U1-5C)") (class "Default")
      (node (ref "U1") (pin "14") (pinfunction "5C_14") (pintype "passive"))
      (node (ref "X1") (pin "6") (pinfunction "1_6") (pintype "passive"))
    )
    (net (code "79") (name "Net-(U1-6C)") (class "Default")
      (node (ref "U1") (pin "13") (pinfunction "6C_13") (pintype "passive"))
      (node (ref "X1") (pin "13") (pinfunction "1_13") (pintype "passive"))
    )
    (net (code "80") (name "Net-(U1-7C)") (class "Default")
      (node (ref "U1") (pin "12") (pinfunction "7C_12") (pintype "passive"))
      (node (ref "X1") (pin "14") (pinfunction "1_14") (pintype "passive"))
    )
    (net (code "81") (name "Net-(U1-8C)") (class "Default")
      (node (ref "U1") (pin "11") (pinfunction "8C_11") (pintype "passive"))
      (node (ref "X1") (pin "15") (pinfunction "1_15") (pintype "passive"))
    )
    (net (code "82") (name "Net-(U2-1C)") (class "Default")
      (node (ref "U2") (pin "18") (pinfunction "1C_18") (pintype "passive"))
      (node (ref "X1") (pin "12") (pinfunction "1_12") (pintype "passive"))
    )
    (net (code "83") (name "Net-(U2-2C)") (class "Default")
      (node (ref "U2") (pin "17") (pinfunction "2C_17") (pintype "passive"))
      (node (ref "X1") (pin "11") (pinfunction "1_11") (pintype "passive"))
    )
    (net (code "84") (name "Net-(U2-3C)") (class "Default")
      (node (ref "U2") (pin "16") (pinfunction "3C_16") (pintype "passive"))
      (node (ref "X1") (pin "10") (pinfunction "1_10") (pintype "passive"))
    )
    (net (code "85") (name "Net-(U2-4C)") (class "Default")
      (node (ref "U2") (pin "15") (pinfunction "4C_15") (pintype "passive"))
      (node (ref "X1") (pin "9") (pinfunction "1_9") (pintype "passive"))
    )
    (net (code "86") (name "Net-(U4-ADECAY)") (class "Default")
      (node (ref "R10") (pin "1") (pinfunction "1_1") (pintype "passive"))
      (node (ref "U4") (pin "3") (pinfunction "ADECAY_3") (pintype "input"))
    )
    (net (code "87") (name "Net-(U4-AISEN)") (class "Default")
      (node (ref "R16") (pin "1") (pinfunction "1_1") (pintype "passive"))
      (node (ref "U4") (pin "5") (pinfunction "AISEN_5") (pintype "bidirectional"))
    )
    (net (code "88") (name "Net-(U4-AOUT1)") (class "Default")
      (node (ref "J3") (pin "4") (pinfunction "4_4") (pintype "passive"))
      (node (ref "J4") (pin "4") (pinfunction "4_4") (pintype "passive"))
      (node (ref "U4") (pin "4") (pinfunction "AOUT1_4") (pintype "output"))
    )
    (net (code "89") (name "Net-(U4-AOUT2)") (class "Default")
      (node (ref "J3") (pin "3") (pinfunction "3_3") (pintype "passive"))
      (node (ref "J4") (pin "3") (pinfunction "3_3") (pintype "passive"))
      (node (ref "U4") (pin "6") (pinfunction "AOUT2_6") (pintype "output"))
    )
    (net (code "90") (name "Net-(U4-BDECAY)") (class "Default")
      (node (ref "R17") (pin "1") (pinfunction "1_1") (pintype "passive"))
      (node (ref "U4") (pin "2") (pinfunction "BDECAY_2") (pintype "input"))
    )
    (net (code "91") (name "Net-(U4-BISEN)") (class "Default")
      (node (ref "R15") (pin "1") (pinfunction "1_1") (pintype "passive"))
      (node (ref "U4") (pin "8") (pinfunction "BISEN_8") (pintype "bidirectional"))
    )
    (net (code "92") (name "Net-(U4-BOUT1)") (class "Default")
      (node (ref "J3") (pin "2") (pinfunction "2_2") (pintype "passive"))
      (node (ref "J4") (pin "1") (pinfunction "1_1") (pintype "passive"))
      (node (ref "U4") (pin "9") (pinfunction "BOUT1_9") (pintype "output"))
    )
    (net (code "93") (name "Net-(U4-BOUT2)") (class "Default")
      (node (ref "J3") (pin "1") (pinfunction "1_1") (pintype "passive"))
      (node (ref "J4") (pin "2") (pinfunction "2_2") (pintype "passive"))
      (node (ref "U4") (pin "7") (pinfunction "BOUT2_7") (pintype "output"))
    )
    (net (code "94") (name "Net-(U4-M0{slash}APHASE)") (class "Default")
      (node (ref "M02") (pin "1") (pinfunction "1_1") (pintype "passive"))
      (node (ref "U4") (pin "13") (pinfunction "M0/APHASE_13") (pintype "input"))
    )
    (net (code "95") (name "Net-(U4-M1)") (class "Default")
      (node (ref "M12") (pin "1") (pinfunction "1_1") (pintype "passive"))
      (node (ref "U4") (pin "14") (pinfunction "M1_14") (pintype "input"))
    )
    (net (code "96") (name "Net-(U4-NFAULT)") (class "Default")
      (node (ref "R18") (pin "1") (pinfunction "1_1") (pintype "passive"))
      (node (ref "U4") (pin "16") (pinfunction "NFAULT_16") (pintype "output"))
    )
    (net (code "97") (name "Net-(U4-NSLEEP)") (class "Default")
      (node (ref "R19") (pin "1") (pinfunction "1_1") (pintype "passive"))
      (node (ref "U4") (pin "1") (pinfunction "NSLEEP_1") (pintype "input"))
    )
    (net (code "98") (name "Net-(U4-VCP)") (class "Default")
      (node (ref "C9") (pin "1") (pinfunction "1_1") (pintype "passive"))
      (node (ref "U4") (pin "17") (pinfunction "VCP_17") (pintype "output"))
    )
    (net (code "99") (name "Net-(U5-ADECAY)") (class "Default")
      (node (ref "R2") (pin "1") (pinfunction "1_1") (pintype "passive"))
      (node (ref "U5") (pin "3") (pinfunction "ADECAY_3") (pintype "input"))
    )
    (net (code "100") (name "Net-(U5-AISEN)") (class "Default")
      (node (ref "R4") (pin "1") (pinfunction "1_1") (pintype "passive"))
      (node (ref "U5") (pin "5") (pinfunction "AISEN_5") (pintype "bidirectional"))
    )
    (net (code "101") (name "Net-(U5-AOUT1)") (class "Default")
      (node (ref "J2") (pin "4") (pinfunction "4_4") (pintype "passive"))
      (node (ref "J5") (pin "4") (pinfunction "4_4") (pintype "passive"))
      (node (ref "U5") (pin "4") (pinfunction "AOUT1_4") (pintype "output"))
    )
    (net (code "102") (name "Net-(U5-AOUT2)") (class "Default")
      (node (ref "J2") (pin "3") (pinfunction "3_3") (pintype "passive"))
      (node (ref "J5") (pin "3") (pinfunction "3_3") (pintype "passive"))
      (node (ref "U5") (pin "6") (pinfunction "AOUT2_6") (pintype "output"))
    )
    (net (code "103") (name "Net-(U5-BDECAY)") (class "Default")
      (node (ref "R5") (pin "1") (pinfunction "1_1") (pintype "passive"))
      (node (ref "U5") (pin "2") (pinfunction "BDECAY_2") (pintype "input"))
    )
    (net (code "104") (name "Net-(U5-BISEN)") (class "Default")
      (node (ref "R3") (pin "1") (pinfunction "1_1") (pintype "passive"))
      (node (ref "U5") (pin "8") (pinfunction "BISEN_8") (pintype "bidirectional"))
    )
    (net (code "105") (name "Net-(U5-BOUT1)") (class "Default")
      (node (ref "J2") (pin "2") (pinfunction "2_2") (pintype "passive"))
      (node (ref "J5") (pin "1") (pinfunction "1_1") (pintype "passive"))
      (node (ref "U5") (pin "9") (pinfunction "BOUT1_9") (pintype "output"))
    )
    (net (code "106") (name "Net-(U5-BOUT2)") (class "Default")
      (node (ref "J2") (pin "1") (pinfunction "1_1") (pintype "passive"))
      (node (ref "J5") (pin "2") (pinfunction "2_2") (pintype "passive"))
      (node (ref "U5") (pin "7") (pinfunction "BOUT2_7") (pintype "output"))
    )
    (net (code "107") (name "Net-(U5-M0{slash}APHASE)") (class "Default")
      (node (ref "M01") (pin "1") (pinfunction "1_1") (pintype "passive"))
      (node (ref "U5") (pin "13") (pinfunction "M0/APHASE_13") (pintype "input"))
    )
    (net (code "108") (name "Net-(U5-M1)") (class "Default")
      (node (ref "M11") (pin "1") (pinfunction "1_1") (pintype "passive"))
      (node (ref "U5") (pin "14") (pinfunction "M1_14") (pintype "input"))
    )
    (net (code "109") (name "Net-(U5-NFAULT)") (class "Default")
      (node (ref "R8") (pin "1") (pinfunction "1_1") (pintype "passive"))
      (node (ref "U5") (pin "16") (pinfunction "NFAULT_16") (pintype "output"))
    )
    (net (code "110") (name "Net-(U5-NSLEEP)") (class "Default")
      (node (ref "R9") (pin "1") (pinfunction "1_1") (pintype "passive"))
      (node (ref "U5") (pin "1") (pinfunction "NSLEEP_1") (pintype "input"))
    )
    (net (code "111") (name "Net-(U5-VCP)") (class "Default")
      (node (ref "C11") (pin "1") (pinfunction "1_1") (pintype "passive"))
      (node (ref "U5") (pin "17") (pinfunction "VCP_17") (pintype "output"))
    )
    (net (code "112") (name "Net-(U7-PB6(XTAL1{slash}TOSC1))") (class "Default")
      (node (ref "U7") (pin "7") (pinfunction "PB6(XTAL1/TOSC1)_7") (pintype "bidirectional"))
      (node (ref "Y1") (pin "1") (pinfunction "1_1") (pintype "passive"))
    )
    (net (code "113") (name "Net-(U7-PB7(XTAL2{slash}TOSC2))") (class "Default")
      (node (ref "U7") (pin "8") (pinfunction "PB7(XTAL2/TOSC2)_8") (pintype "bidirectional"))
      (node (ref "Y1") (pin "3") (pinfunction "3_3") (pintype "passive"))
    )
    (net (code "114") (name "Net-(U7-PD7(AIN1))") (class "Default")
      (node (ref "LED6") (pin "A") (pinfunction "A_A") (pintype "passive"))
      (node (ref "U7") (pin "11") (pinfunction "PD7(AIN1)_11") (pintype "bidirectional"))
    )
    (net (code "115") (name "REF1") (class "Default")
      (node (ref "TM1") (pin "2") (pinfunction "S_2") (pintype "passive"))
      (node (ref "U4") (pin "22") (pinfunction "AVREF_22") (pintype "input"))
      (node (ref "U4") (pin "23") (pinfunction "BVREF_23") (pintype "input"))
    )
    (net (code "116") (name "REF2") (class "Default")
      (node (ref "TM2") (pin "2") (pinfunction "S_2") (pintype "passive"))
      (node (ref "U5") (pin "22") (pinfunction "AVREF_22") (pintype "input"))
      (node (ref "U5") (pin "23") (pinfunction "BVREF_23") (pintype "input"))
    )
    (net (code "117") (name "VCC") (class "Default")
      (node (ref "C17") (pin "+") (pinfunction "+_+") (pintype "passive"))
      (node (ref "C21") (pin "1") (pinfunction "1_1") (pintype "passive"))
      (node (ref "C22") (pin "1") (pinfunction "1_1") (pintype "passive"))
      (node (ref "C23") (pin "1") (pinfunction "1_1") (pintype "passive"))
      (node (ref "C5") (pin "1") (pinfunction "1_1") (pintype "passive"))
      (node (ref "L1") (pin "2") (pinfunction "2_2") (pintype "passive"))
      (node (ref "U3") (pin "1") (pinfunction "INPUT_1") (pintype "input"))
      (node (ref "U4") (pin "18") (pinfunction "VM_18") (pintype "power_in"))
      (node (ref "U4") (pin "19") (pinfunction "VM_2_19") (pintype "power_in"))
      (node (ref "U5") (pin "18") (pinfunction "VM_18") (pintype "power_in"))
      (node (ref "U5") (pin "19") (pinfunction "VM_2_19") (pintype "power_in"))
      (node (ref "U8") (pin "1") (pinfunction "1_1") (pintype "passive"))
      (node (ref "VR1") (pin "4") (pinfunction "VIN_4") (pintype "input"))
    )
    (net (code "118") (name "V_BATT") (class "Default")
      (node (ref "J6") (pin "4") (pinfunction "4_4") (pintype "passive"))
      (node (ref "U8") (pin "2") (pinfunction "2_2") (pintype "passive"))
    )
    (net (code "119") (name "unconnected-(J6-Pad2)") (class "Default")
      (node (ref "J6") (pin "2") (pinfunction "2_2") (pintype "passive"))
    )
    (net (code "120") (name "unconnected-(J6-Pad3)") (class "Default")
      (node (ref "J6") (pin "3") (pinfunction "3_3") (pintype "passive"))
    )
    (net (code "121") (name "unconnected-(J10-Pad2)") (class "Default")
      (node (ref "J10") (pin "2") (pinfunction "2_2") (pintype "passive"))
    )
    (net (code "122") (name "unconnected-(U2-5C-Pad14)") (class "Default")
      (node (ref "U2") (pin "14") (pinfunction "5C_14") (pintype "passive"))
    )
    (net (code "123") (name "unconnected-(U2-6C-Pad13)") (class "Default")
      (node (ref "U2") (pin "13") (pinfunction "6C_13") (pintype "passive"))
    )
    (net (code "124") (name "unconnected-(U2-7C-Pad12)") (class "Default")
      (node (ref "U2") (pin "12") (pinfunction "7C_12") (pintype "passive"))
    )
    (net (code "125") (name "unconnected-(U2-8C-Pad11)") (class "Default")
      (node (ref "U2") (pin "11") (pinfunction "8C_11") (pintype "passive"))
    )
    (net (code "126") (name "unconnected-(U6-*GPIO9-PadGPIO9)") (class "Default")
      (node (ref "U6") (pin "GPIO9") (pinfunction "*GPIO9_GPIO9") (pintype "bidirectional"))
    )
    (net (code "127") (name "unconnected-(U6-*GPIO10-PadGPIO10)") (class "Default")
      (node (ref "U6") (pin "GPIO10") (pinfunction "*GPIO10_GPIO10") (pintype "bidirectional"))
    )
    (net (code "128") (name "unconnected-(U6-PadADC)") (class "Default")
      (node (ref "U6") (pin "ADC") (pinfunction "ADC_ADC") (pintype "bidirectional"))
    )
    (net (code "129") (name "unconnected-(U6-PadCS0)") (class "Default")
      (node (ref "U6") (pin "CS0") (pinfunction "CS0_CS0") (pintype "bidirectional"))
    )
    (net (code "130") (name "unconnected-(U6-PadGPIO5)") (class "Default")
      (node (ref "U6") (pin "GPIO5") (pinfunction "GPIO5_GPIO5") (pintype "bidirectional"))
    )
    (net (code "131") (name "unconnected-(U6-PadMISO)") (class "Default")
      (node (ref "U6") (pin "MISO") (pinfunction "MISO_MISO") (pintype "bidirectional"))
    )
    (net (code "132") (name "unconnected-(U6-PadMOSI)") (class "Default")
      (node (ref "U6") (pin "MOSI") (pinfunction "MOSI_MOSI") (pintype "bidirectional"))
    )
    (net (code "133") (name "unconnected-(U6-PadSCLK)") (class "Default")
      (node (ref "U6") (pin "SCLK") (pinfunction "SCLK_SCLK") (pintype "bidirectional"))
    )
    (net (code "134") (name "unconnected-(U7-ADC6-Pad19)") (class "Default")
      (node (ref "U7") (pin "19") (pinfunction "ADC6_19") (pintype "bidirectional"))
    )
    (net (code "135") (name "unconnected-(U7-ADC7-Pad22)") (class "Default")
      (node (ref "U7") (pin "22") (pinfunction "ADC7_22") (pintype "bidirectional"))
    )
    (net (code "136") (name "unconnected-(U7-AREF-Pad20)") (class "Default")
      (node (ref "U7") (pin "20") (pinfunction "AREF_20") (pintype "bidirectional"))
    )
    (net (code "137") (name "unconnected-(U7-PC5(ADC5{slash}SCL)-Pad28)") (class "Default")
      (node (ref "U7") (pin "28") (pinfunction "PC5(ADC5/SCL)_28") (pintype "bidirectional"))
    )
    (net (code "138") (name "unconnected-(U8-Pad3)") (class "Default")
      (node (ref "U8") (pin "3") (pinfunction "3_3") (pintype "passive"))
    )
    (net (code "139") (name "unconnected-(VR1-EN-Pad2)") (class "Default")
      (node (ref "VR1") (pin "2") (pinfunction "EN_2") (pintype "input"))
    )
    (net (code "140") (name "unconnected-(X1-Pad1)") (class "Default")
      (node (ref "X1") (pin "1") (pinfunction "1_1") (pintype "passive"))
    )
    (net (code "141") (name "unconnected-(X1I-1-Pad2)") (class "Default")
      (node (ref "X1") (pin "2") (pinfunction "1_2") (pintype "passive"))
    )
  )
)
